# source_eagle.net
KiCad netlist of a schematic drawn in EAGLE
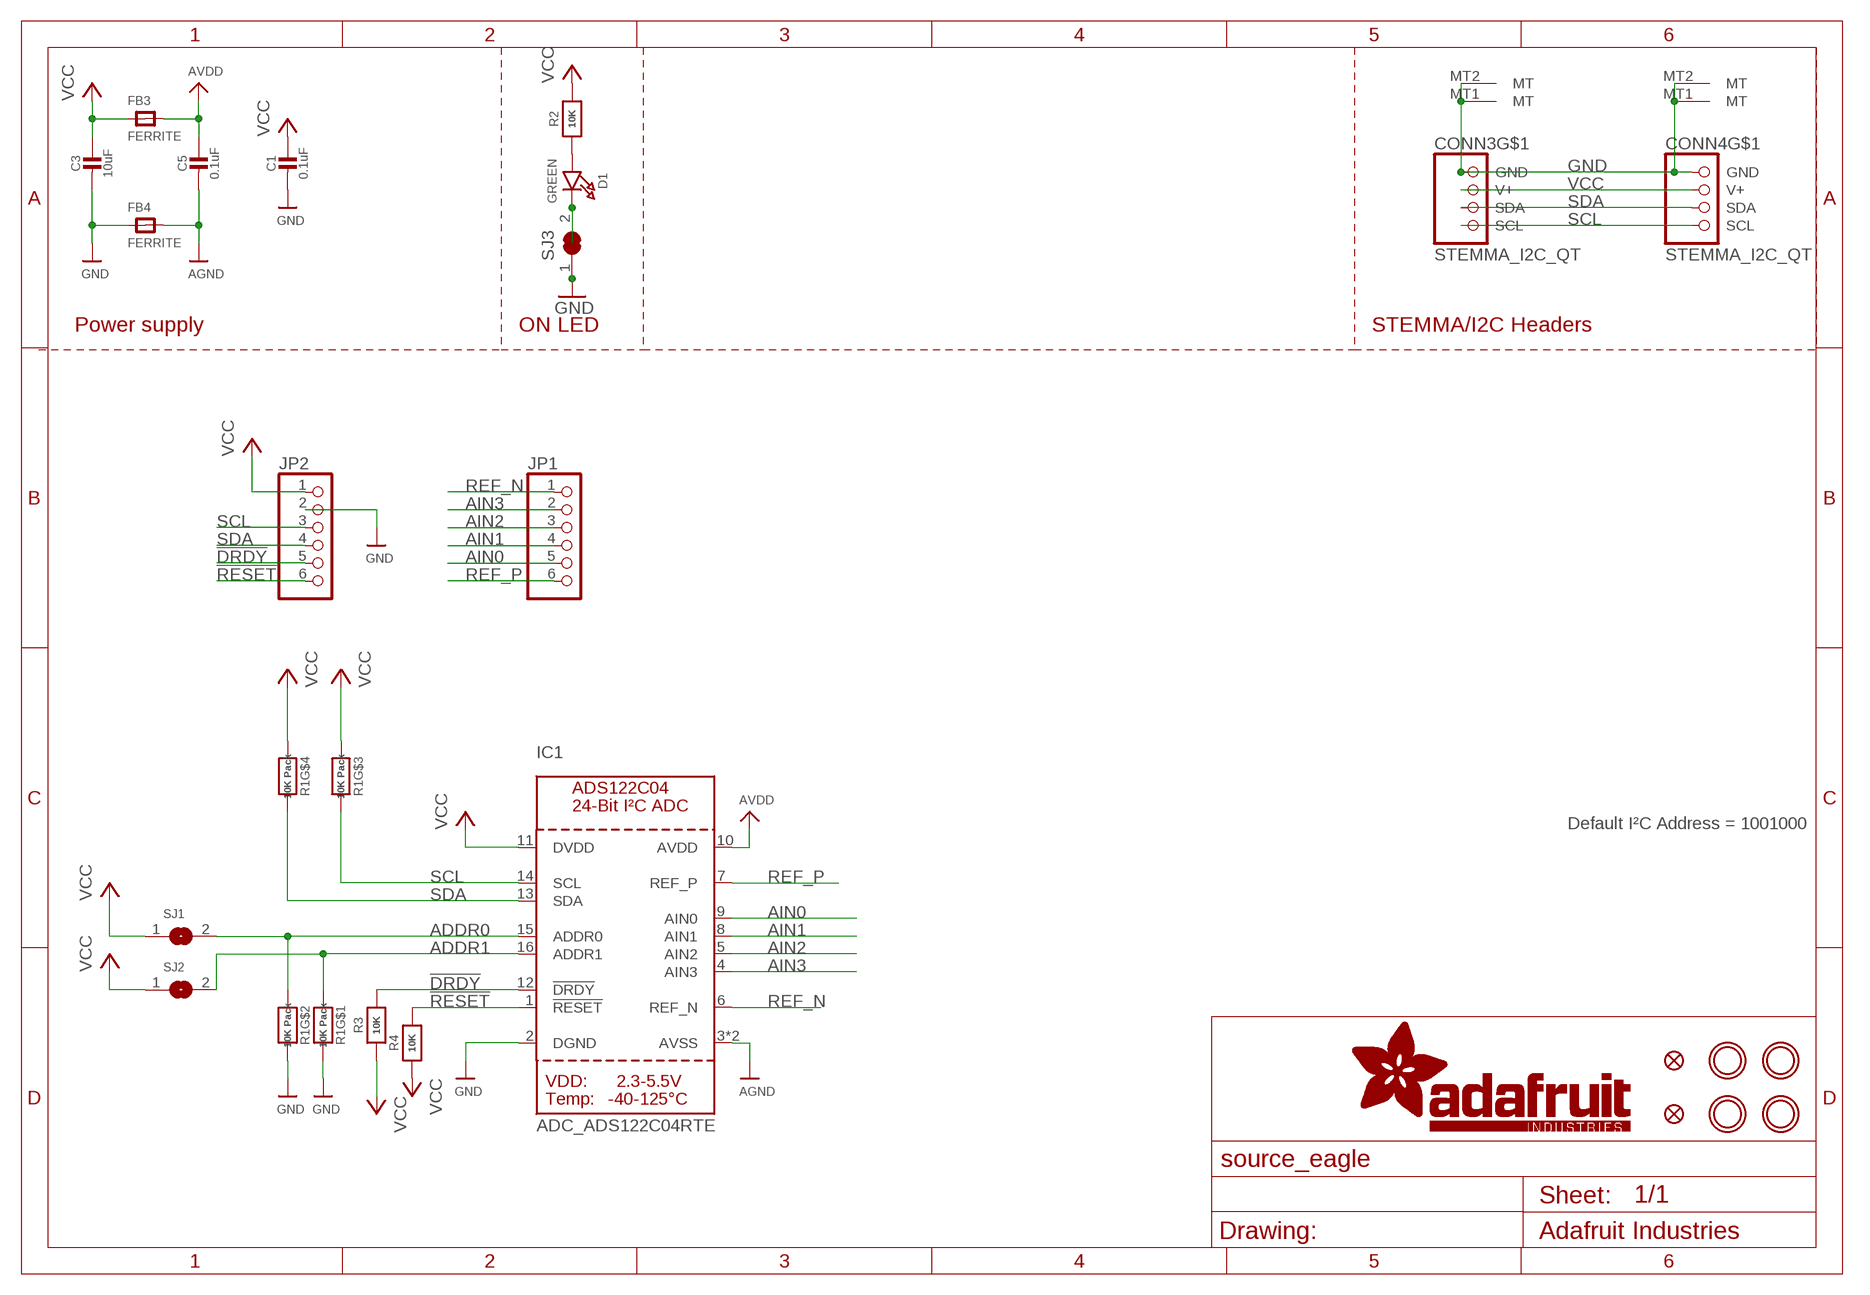
[diagram p0: schematic, sheet 1]

(export (version "E")
  (design (tool "Eeschema 10.0.6"))
  (components
    (comp (ref "C1")
      (value "0.1uF")
      (footprint "eagle-import:0603-NO")
      (libsource (lib "eagle-import") (part "CAP_CERAMIC0603_NO"))
    )
    (comp (ref "C3")
      (value "10uF")
      (footprint "eagle-import:0805-NO")
      (libsource (lib "eagle-import") (part "CAP_CERAMIC0805-NOOUTLINE"))
    )
    (comp (ref "C5")
      (value "0.1uF")
      (footprint "eagle-import:0603-NO")
      (libsource (lib "eagle-import") (part "CAP_CERAMIC0603_NO"))
    )
    (comp (ref "CONN3")
      (value "STEMMA_I2C_QT")
      (footprint "eagle-import:JST_SH4")
      (libsource (lib "eagle-import") (part "STEMMA_I2C_QT"))
    )
    (comp (ref "CONN4")
      (value "STEMMA_I2C_QT")
      (footprint "eagle-import:JST_SH4")
      (libsource (lib "eagle-import") (part "STEMMA_I2C_QT"))
    )
    (comp (ref "D1")
      (value "GREEN")
      (footprint "eagle-import:CHIPLED_0603_NOOUTLINE")
      (libsource (lib "eagle-import") (part "LED0603_NOOUTLINE"))
    )
    (comp (ref "FB3")
      (value "FERRITE")
      (footprint "eagle-import:0603-NO")
      (libsource (lib "eagle-import") (part "FERRITE-0603NO"))
    )
    (comp (ref "FB4")
      (value "FERRITE")
      (footprint "eagle-import:0603-NO")
      (libsource (lib "eagle-import") (part "FERRITE-0603NO"))
    )
    (comp (ref "FID3")
      (value "FIDUCIAL_0.5MM")
      (footprint "eagle-import:FIDUCIAL_0.5MM")
      (libsource (lib "eagle-import") (part "FIDUCIAL_0.5MM"))
    )
    (comp (ref "FID4")
      (value "FIDUCIAL_0.5MM")
      (footprint "eagle-import:FIDUCIAL_0.5MM")
      (libsource (lib "eagle-import") (part "FIDUCIAL_0.5MM"))
    )
    (comp (ref "IC1")
      (value "ADC_ADS122C04RTE")
      (footprint "eagle-import:WQFN16")
      (libsource (lib "eagle-import") (part "ADC_ADS122C04RTE"))
    )
    (comp (ref "JP1")
      (value "HEADER-1X670MIL")
      (footprint "eagle-import:1X06_ROUND_70")
      (libsource (lib "eagle-import") (part "HEADER-1X670MIL"))
    )
    (comp (ref "JP2")
      (value "HEADER-1X670MIL")
      (footprint "eagle-import:1X06_ROUND_70")
      (libsource (lib "eagle-import") (part "HEADER-1X670MIL"))
    )
    (comp (ref "R1")
      (value "10K Pack")
      (footprint "eagle-import:RESPACK_4X0603")
      (libsource (lib "eagle-import") (part "RESISTOR_4PACK"))
    )
    (comp (ref "R2")
      (value "10K")
      (footprint "eagle-import:0603-NO")
      (libsource (lib "eagle-import") (part "RESISTOR_0603_NOOUT"))
    )
    (comp (ref "R3")
      (value "10K")
      (footprint "eagle-import:0603-NO")
      (libsource (lib "eagle-import") (part "RESISTOR_0603_NOOUT"))
    )
    (comp (ref "R4")
      (value "10K")
      (footprint "eagle-import:0603-NO")
      (libsource (lib "eagle-import") (part "RESISTOR_0603_NOOUT"))
    )
    (comp (ref "SJ1")
      (value "SOLDERJUMPER")
      (footprint "eagle-import:SOLDERJUMPER_ARROW_NOPASTE")
      (libsource (lib "eagle-import") (part "SOLDERJUMPER"))
    )
    (comp (ref "SJ2")
      (value "SOLDERJUMPER")
      (footprint "eagle-import:SOLDERJUMPER_ARROW_NOPASTE")
      (libsource (lib "eagle-import") (part "SOLDERJUMPER"))
    )
    (comp (ref "SJ3")
      (value "SOLDERJUMPER_CLOSED")
      (footprint "eagle-import:SOLDERJUMPER_CLOSEDWIRE")
      (libsource (lib "eagle-import") (part "SOLDERJUMPER_CLOSED"))
    )
    (comp (ref "U$25")
      (value "MOUNTINGHOLE2.5")
      (footprint "eagle-import:MOUNTINGHOLE_2.5_PLATED")
      (libsource (lib "eagle-import") (part "MOUNTINGHOLE2.5"))
    )
    (comp (ref "U$27")
      (value "MOUNTINGHOLE2.5")
      (footprint "eagle-import:MOUNTINGHOLE_2.5_PLATED")
      (libsource (lib "eagle-import") (part "MOUNTINGHOLE2.5"))
    )
    (comp (ref "U$29")
      (value "MOUNTINGHOLE2.5")
      (footprint "eagle-import:MOUNTINGHOLE_2.5_PLATED")
      (libsource (lib "eagle-import") (part "MOUNTINGHOLE2.5"))
    )
    (comp (ref "U$30")
      (value "MOUNTINGHOLE2.5")
      (footprint "eagle-import:MOUNTINGHOLE_2.5_PLATED")
      (libsource (lib "eagle-import") (part "MOUNTINGHOLE2.5"))
    )
  )
  (nets
    (net (code "1") (name "/ADDR0") (class "Default")
      (node (ref "IC1") (pin "15") (pinfunction "ADDR0_15") (pintype "input"))
      (node (ref "R1") (pin "2") (pinfunction "1_2") (pintype "passive"))
      (node (ref "SJ1") (pin "2") (pinfunction "2_2") (pintype "passive"))
    )
    (net (code "2") (name "/ADDR1") (class "Default")
      (node (ref "IC1") (pin "16") (pinfunction "ADDR1_16") (pintype "input"))
      (node (ref "R1") (pin "1") (pinfunction "1_1") (pintype "passive"))
      (node (ref "SJ2") (pin "2") (pinfunction "2_2") (pintype "passive"))
    )
    (net (code "3") (name "/AIN0") (class "Default")
      (node (ref "IC1") (pin "9") (pinfunction "AIN0_9") (pintype "input"))
      (node (ref "JP1") (pin "5") (pinfunction "5_5") (pintype "passive"))
    )
    (net (code "4") (name "/AIN1") (class "Default")
      (node (ref "IC1") (pin "8") (pinfunction "AIN1_8") (pintype "input"))
      (node (ref "JP1") (pin "4") (pinfunction "4_4") (pintype "passive"))
    )
    (net (code "5") (name "/AIN2") (class "Default")
      (node (ref "IC1") (pin "5") (pinfunction "AIN2_5") (pintype "input"))
      (node (ref "JP1") (pin "3") (pinfunction "3_3") (pintype "passive"))
    )
    (net (code "6") (name "/AIN3") (class "Default")
      (node (ref "IC1") (pin "4") (pinfunction "AIN3_4") (pintype "input"))
      (node (ref "JP1") (pin "2") (pinfunction "2_2") (pintype "passive"))
    )
    (net (code "7") (name "/REF_N") (class "Default")
      (node (ref "IC1") (pin "6") (pinfunction "REF_N_6") (pintype "input"))
      (node (ref "JP1") (pin "1") (pinfunction "1_1") (pintype "passive"))
    )
    (net (code "8") (name "/REF_P") (class "Default")
      (node (ref "IC1") (pin "7") (pinfunction "REF_P_7") (pintype "input"))
      (node (ref "JP1") (pin "6") (pinfunction "6_6") (pintype "passive"))
    )
    (net (code "9") (name "/SCL") (class "Default")
      (node (ref "CONN3") (pin "4") (pinfunction "SCL_4") (pintype "passive"))
      (node (ref "CONN4") (pin "4") (pinfunction "SCL_4") (pintype "passive"))
      (node (ref "IC1") (pin "14") (pinfunction "SCL_14") (pintype "bidirectional"))
      (node (ref "JP2") (pin "3") (pinfunction "3_3") (pintype "passive"))
      (node (ref "R1") (pin "3") (pinfunction "1_3") (pintype "passive"))
    )
    (net (code "10") (name "/SDA") (class "Default")
      (node (ref "CONN3") (pin "3") (pinfunction "SDA_3") (pintype "passive"))
      (node (ref "CONN4") (pin "3") (pinfunction "SDA_3") (pintype "passive"))
      (node (ref "IC1") (pin "13") (pinfunction "SDA_13") (pintype "bidirectional"))
      (node (ref "JP2") (pin "4") (pinfunction "4_4") (pintype "passive"))
      (node (ref "R1") (pin "4") (pinfunction "1_4") (pintype "passive"))
    )
    (net (code "11") (name "/~{DRDY}") (class "Default")
      (node (ref "IC1") (pin "12") (pinfunction "~{DRDY}_12") (pintype "output"))
      (node (ref "JP2") (pin "5") (pinfunction "5_5") (pintype "passive"))
      (node (ref "R3") (pin "2") (pinfunction "2_2") (pintype "passive"))
    )
    (net (code "12") (name "/~{RESET}") (class "Default")
      (node (ref "IC1") (pin "1") (pinfunction "~{RESET}_1") (pintype "input"))
      (node (ref "JP2") (pin "6") (pinfunction "6_6") (pintype "passive"))
      (node (ref "R4") (pin "2") (pinfunction "2_2") (pintype "passive"))
    )
    (net (code "13") (name "AGND") (class "Default")
      (node (ref "C5") (pin "2") (pinfunction "2_2") (pintype "passive"))
      (node (ref "FB4") (pin "2") (pinfunction "P$2_2") (pintype "passive"))
      (node (ref "IC1") (pin "3") (pinfunction "AVSS_3") (pintype "power_in"))
      (node (ref "IC1") (pin "THERM") (pinfunction "AVSS_THERM") (pintype "power_in"))
    )
    (net (code "14") (name "AVDD") (class "Default")
      (node (ref "C5") (pin "1") (pinfunction "1_1") (pintype "passive"))
      (node (ref "FB3") (pin "2") (pinfunction "P$2_2") (pintype "passive"))
      (node (ref "IC1") (pin "10") (pinfunction "AVDD_10") (pintype "power_in"))
    )
    (net (code "15") (name "GND") (class "Default")
      (node (ref "C1") (pin "2") (pinfunction "2_2") (pintype "passive"))
      (node (ref "C3") (pin "2") (pinfunction "2_2") (pintype "passive"))
      (node (ref "CONN3") (pin "1") (pinfunction "GND_1") (pintype "passive"))
      (node (ref "CONN3") (pin "MT1") (pinfunction "MT_MT1") (pintype "bidirectional"))
      (node (ref "CONN3") (pin "MT2") (pinfunction "MT_MT2") (pintype "bidirectional"))
      (node (ref "CONN4") (pin "1") (pinfunction "GND_1") (pintype "passive"))
      (node (ref "CONN4") (pin "MT1") (pinfunction "MT_MT1") (pintype "bidirectional"))
      (node (ref "CONN4") (pin "MT2") (pinfunction "MT_MT2") (pintype "bidirectional"))
      (node (ref "FB4") (pin "1") (pinfunction "P$1_1") (pintype "passive"))
      (node (ref "IC1") (pin "2") (pinfunction "DGND_2") (pintype "power_in"))
      (node (ref "JP2") (pin "2") (pinfunction "2_2") (pintype "passive"))
      (node (ref "R1") (pin "7") (pinfunction "2_7") (pintype "passive"))
      (node (ref "R1") (pin "8") (pinfunction "2_8") (pintype "passive"))
      (node (ref "SJ3") (pin "1") (pinfunction "1_1") (pintype "passive"))
    )
    (net (code "16") (name "Net-(D1-PadA)") (class "Default")
      (node (ref "D1") (pin "A") (pinfunction "A_A") (pintype "passive"))
      (node (ref "R2") (pin "1") (pinfunction "1_1") (pintype "passive"))
    )
    (net (code "17") (name "Net-(D1-PadC)") (class "Default")
      (node (ref "D1") (pin "C") (pinfunction "C_C") (pintype "passive"))
      (node (ref "SJ3") (pin "2") (pinfunction "2_2") (pintype "passive"))
    )
    (net (code "18") (name "VCC") (class "Default")
      (node (ref "C1") (pin "1") (pinfunction "1_1") (pintype "passive"))
      (node (ref "C3") (pin "1") (pinfunction "1_1") (pintype "passive"))
      (node (ref "CONN3") (pin "2") (pinfunction "V+_2") (pintype "passive"))
      (node (ref "CONN4") (pin "2") (pinfunction "V+_2") (pintype "passive"))
      (node (ref "FB3") (pin "1") (pinfunction "P$1_1") (pintype "passive"))
      (node (ref "IC1") (pin "11") (pinfunction "DVDD_11") (pintype "power_in"))
      (node (ref "JP2") (pin "1") (pinfunction "1_1") (pintype "passive"))
      (node (ref "R1") (pin "5") (pinfunction "2_5") (pintype "passive"))
      (node (ref "R1") (pin "6") (pinfunction "2_6") (pintype "passive"))
      (node (ref "R2") (pin "2") (pinfunction "2_2") (pintype "passive"))
      (node (ref "R3") (pin "1") (pinfunction "1_1") (pintype "passive"))
      (node (ref "R4") (pin "1") (pinfunction "1_1") (pintype "passive"))
      (node (ref "SJ1") (pin "1") (pinfunction "1_1") (pintype "passive"))
      (node (ref "SJ2") (pin "1") (pinfunction "1_1") (pintype "passive"))
    )
  )
)
